# controller_rev4_1.net
KiCad netlist of a schematic drawn in EAGLE
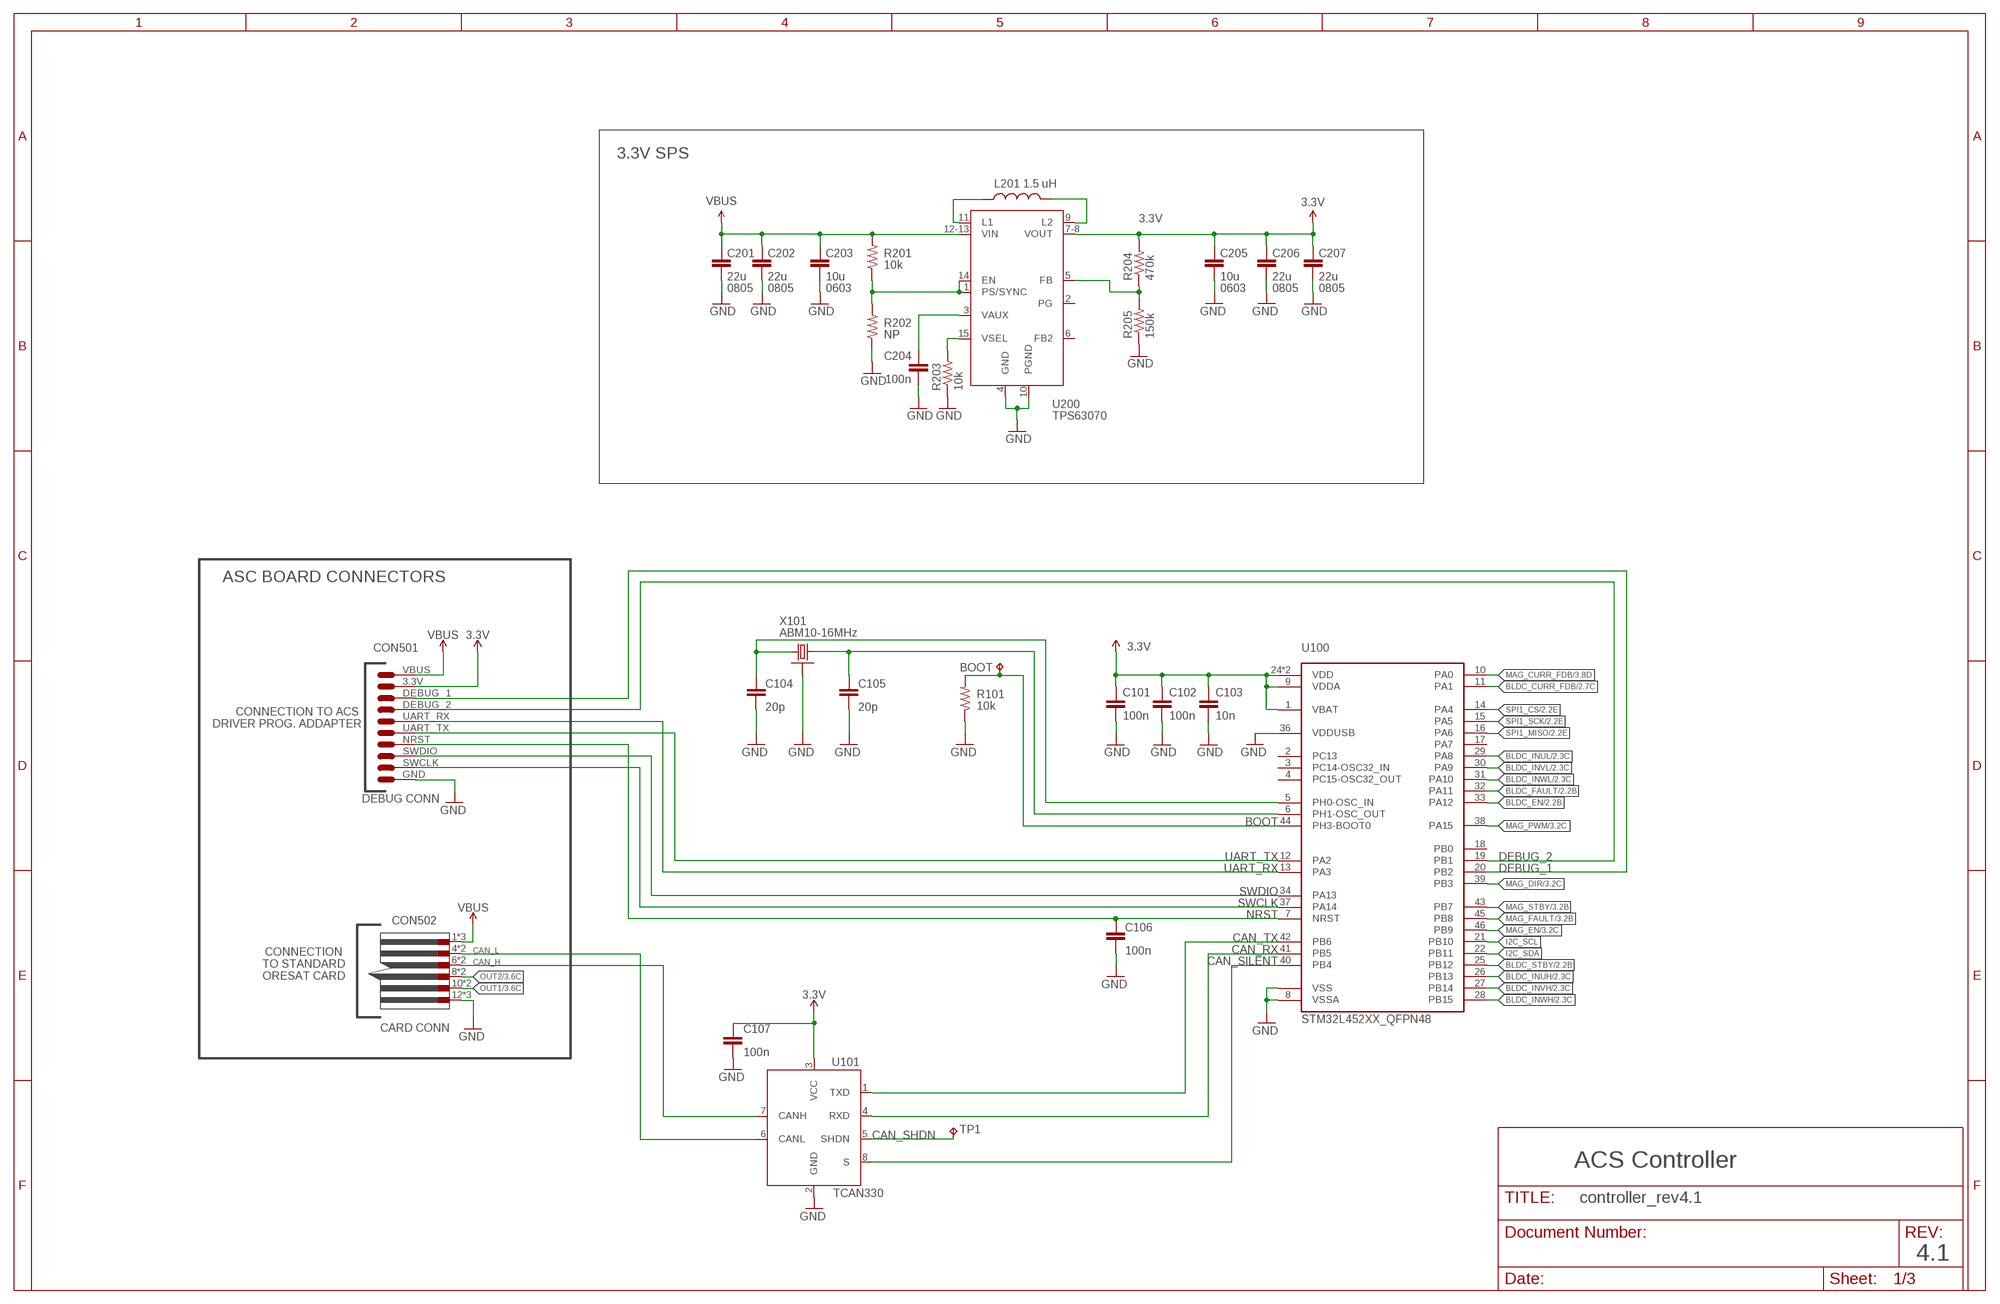
[diagram p0: schematic, sheet 1]
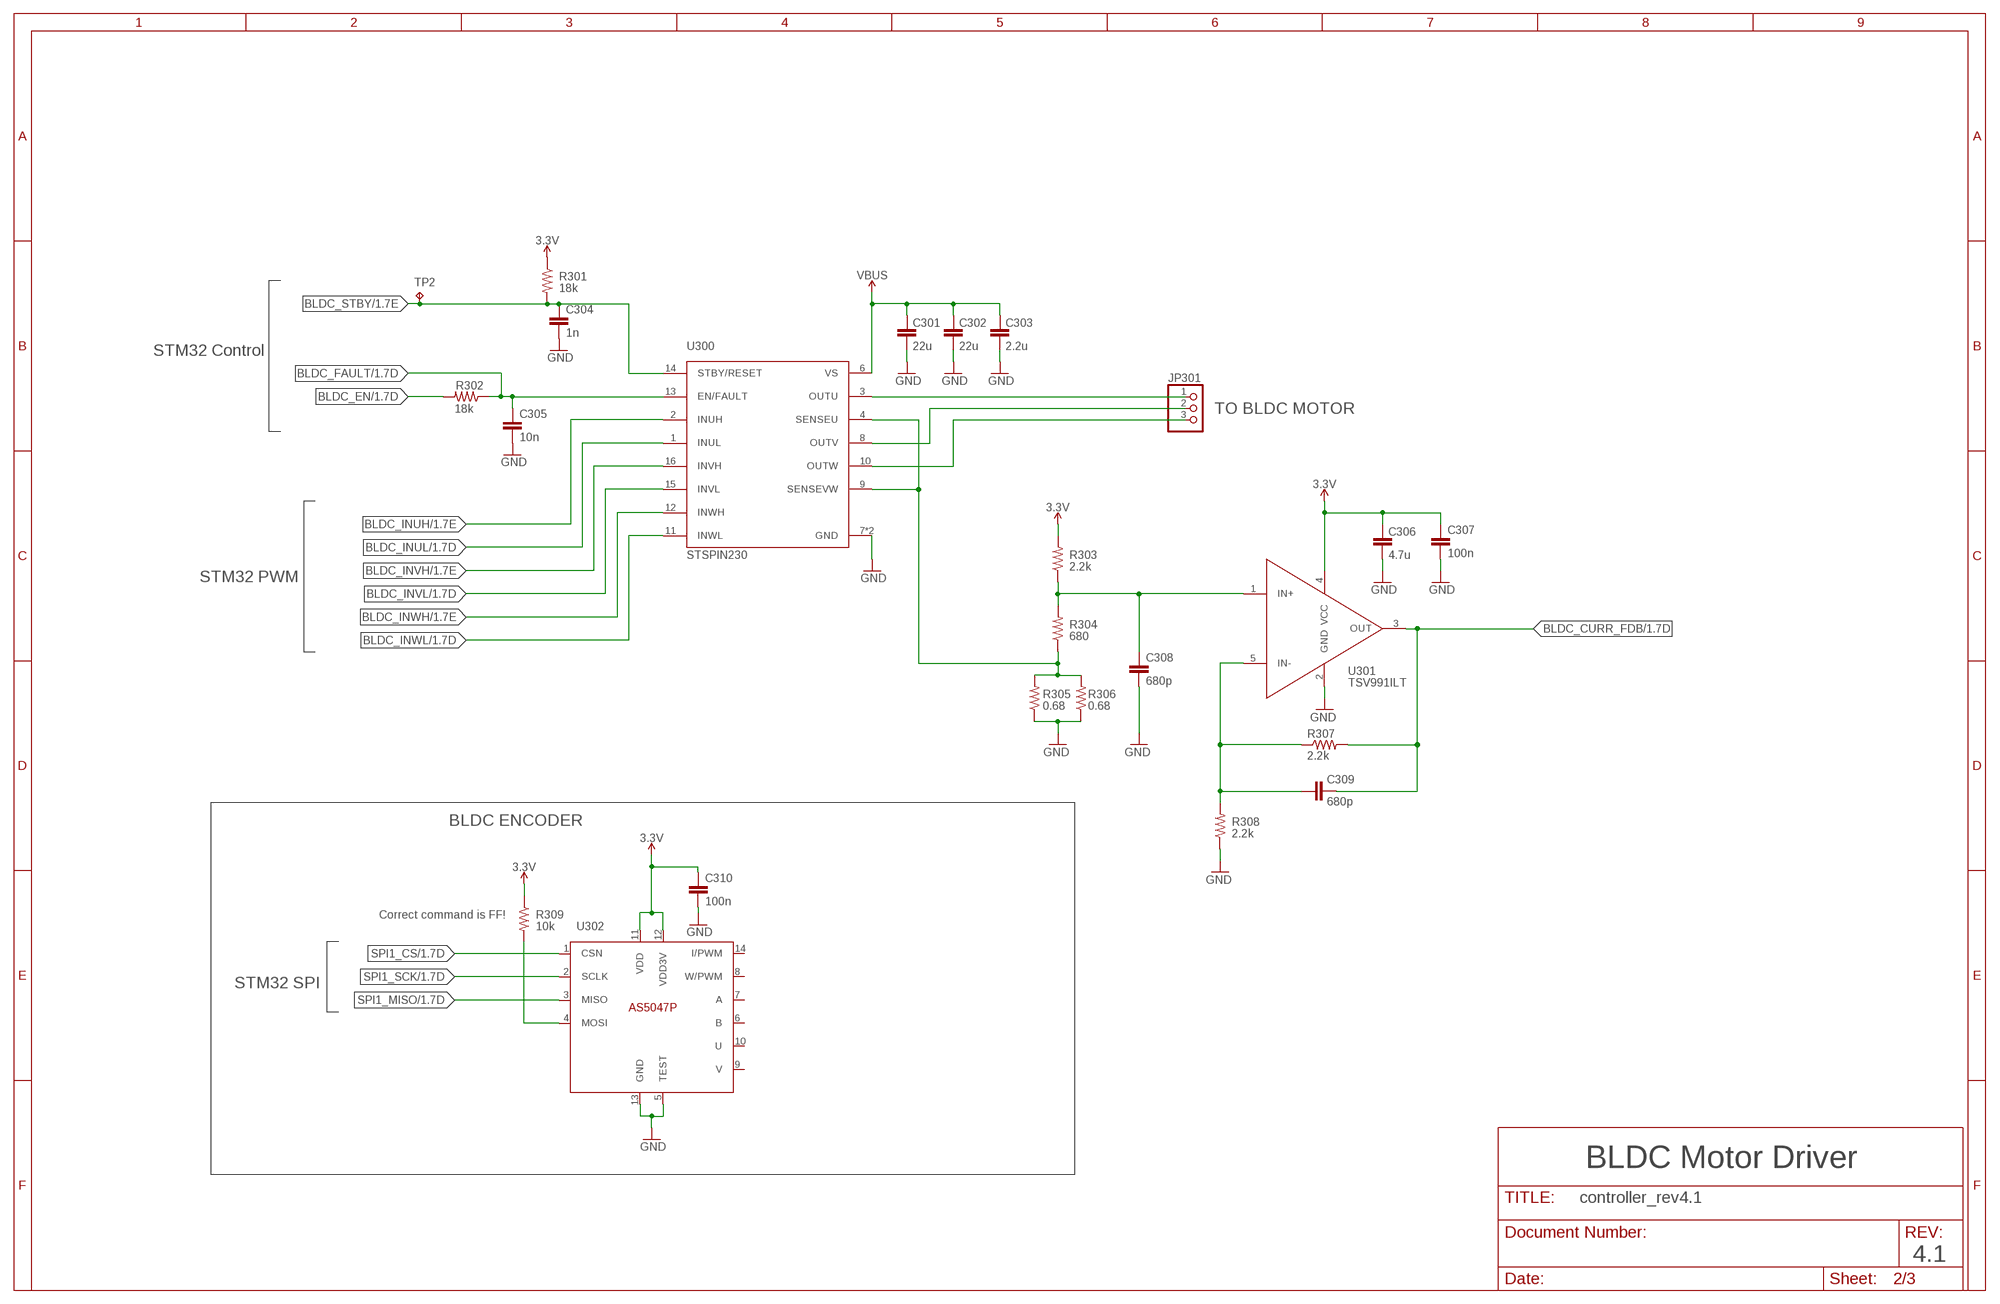
[diagram p1: schematic, sheet 2]
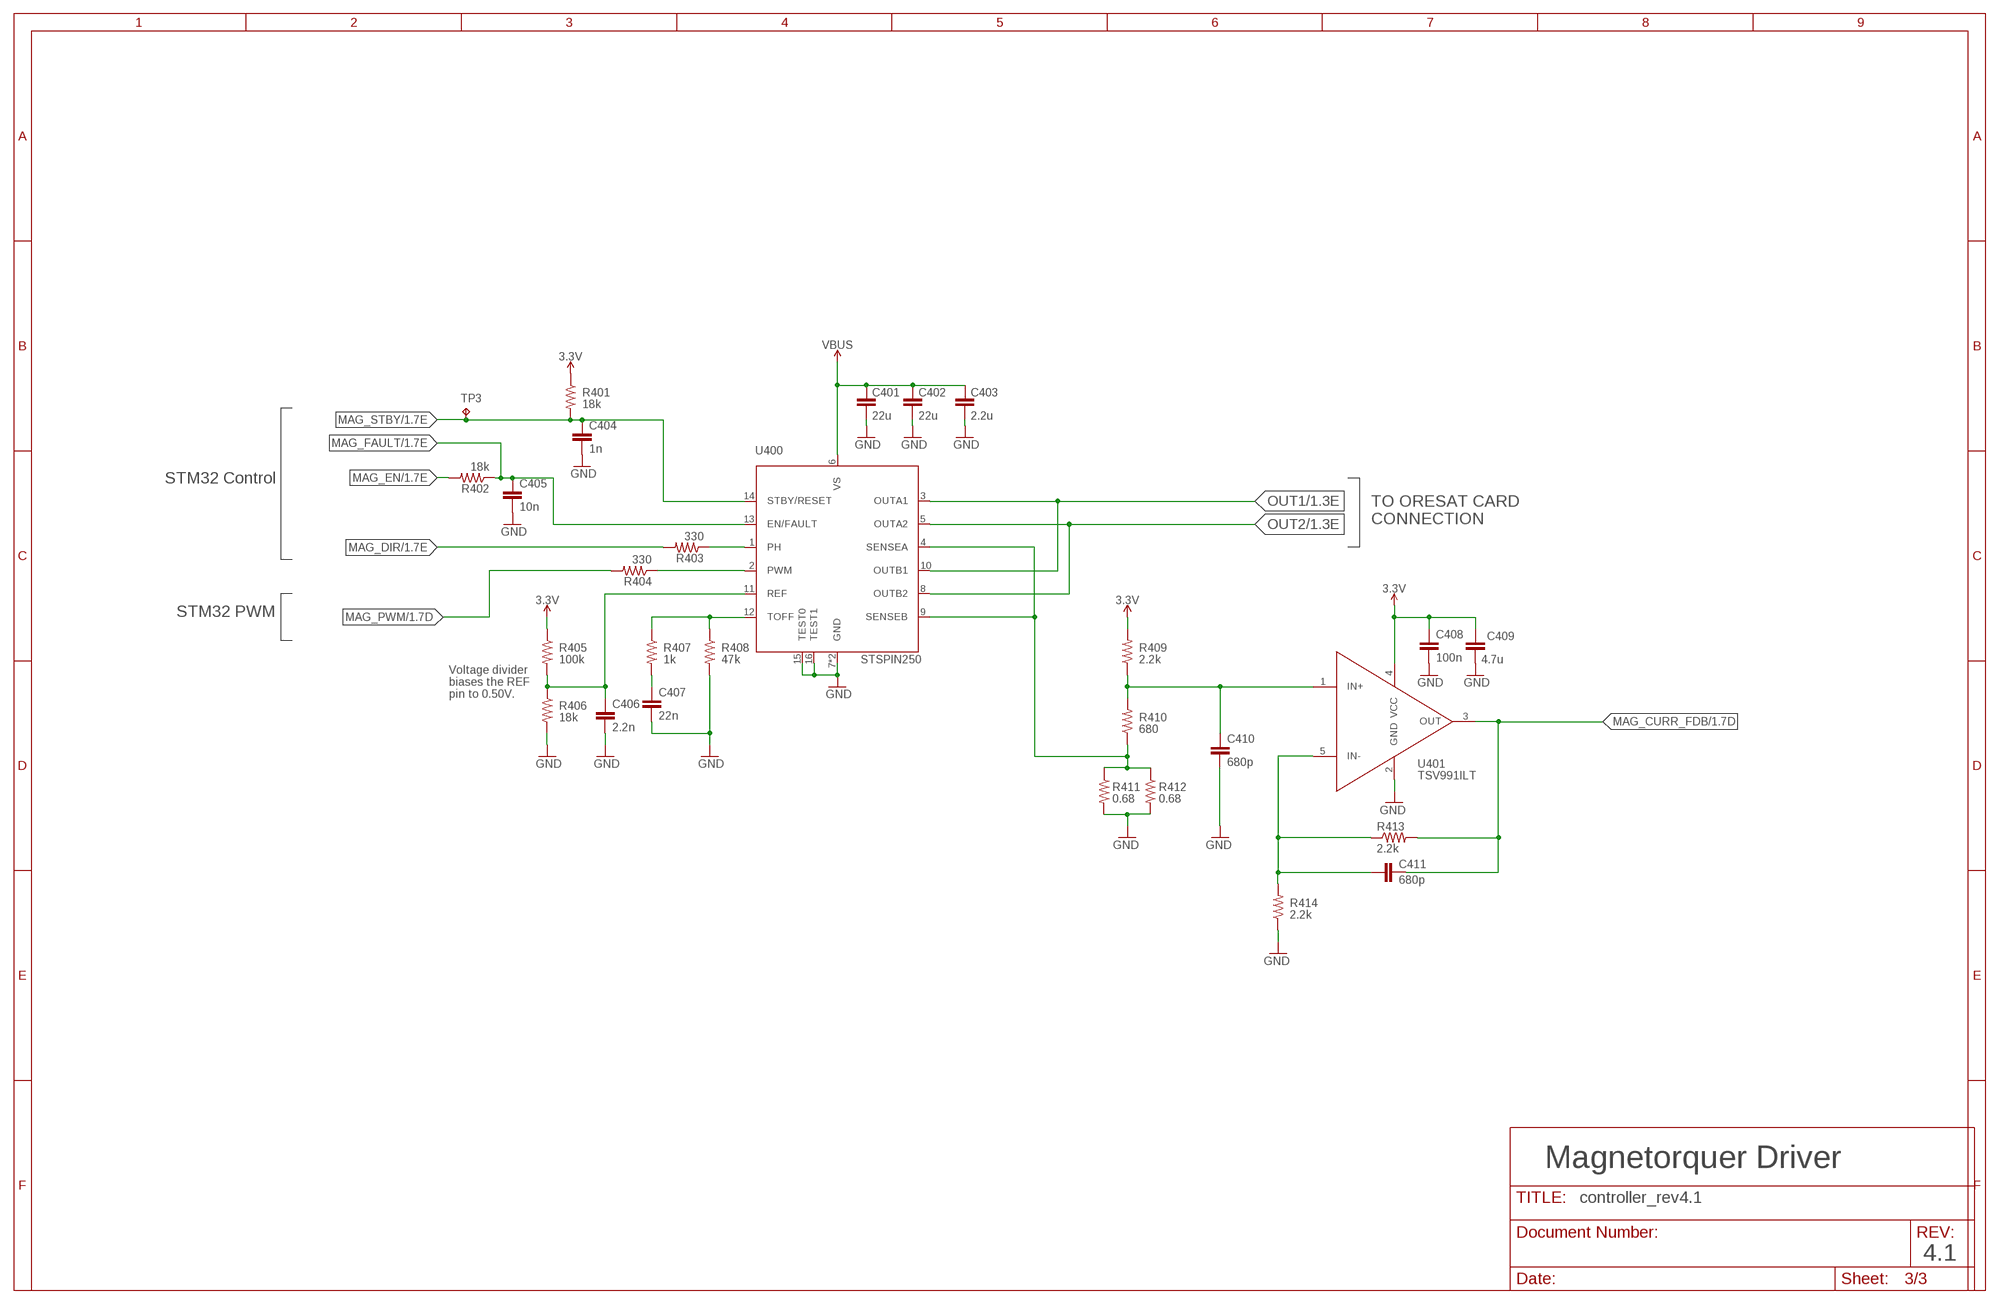
[diagram p2: schematic, sheet 3]

(export (version "E")
  (design (tool "Eeschema 10.0.6"))
  (components
    (comp (ref "C301")
      (value "22u")
      (footprint "eagle-import:.0603-B-NOSILK")
      (fields (field (name "MFR") "Samsung") (field (name "MPN") "CL05B104KO5NNNC"))
      (libsource (lib "eagle-import") (part "C-EU0603-B-NOSILK"))
    )
    (comp (ref "C302")
      (value "22u")
      (footprint "eagle-import:.0603-B-NOSILK")
      (fields (field (name "MFR") "Samsung") (field (name "MPN") "CL05B104KO5NNNC"))
      (libsource (lib "eagle-import") (part "C-EU0603-B-NOSILK"))
    )
    (comp (ref "C303")
      (value "2.2u")
      (footprint "eagle-import:.0603-B-NOSILK")
      (fields (field (name "MFR") "Samsung") (field (name "MPN") "CL05B104KO5NNNC"))
      (libsource (lib "eagle-import") (part "C-EU0603-B-NOSILK"))
    )
    (comp (ref "C304")
      (value "1n")
      (footprint "eagle-import:.0402-B-NOSILK")
      (fields (field (name "MFR") "Samsung") (field (name "MPN") "CL05B104KO5NNNC"))
      (libsource (lib "eagle-import") (part "rcl_custom_C-EU0402-B-NOSILK"))
    )
    (comp (ref "C305")
      (value "10n")
      (footprint "eagle-import:.0402-B-NOSILK")
      (fields (field (name "MFR") "Samsung") (field (name "MPN") "CL05B104KO5NNNC"))
      (libsource (lib "eagle-import") (part "rcl_custom_C-EU0402-B-NOSILK"))
    )
    (comp (ref "C306")
      (value "4.7u")
      (footprint "eagle-import:.0603-B-NOSILK")
      (fields (field (name "MFR") "Samsung") (field (name "MPN") "CL05B104KO5NNNC"))
      (libsource (lib "eagle-import") (part "C-EU0603-B-NOSILK"))
    )
    (comp (ref "C307")
      (value "100n")
      (footprint "eagle-import:.0402-B-NOSILK")
      (fields (field (name "MFR") "Samsung") (field (name "MPN") "CL05B104KO5NNNC"))
      (libsource (lib "eagle-import") (part "rcl_custom_C-EU0402-B-NOSILK"))
    )
    (comp (ref "C308")
      (value "680p")
      (footprint "eagle-import:.0402-B-NOSILK")
      (fields (field (name "MFR") "Samsung") (field (name "MPN") "CL05B104KO5NNNC"))
      (libsource (lib "eagle-import") (part "rcl_custom_C-EU0402-B-NOSILK"))
    )
    (comp (ref "C309")
      (value "680p")
      (footprint "eagle-import:.0402-B-NOSILK")
      (fields (field (name "MFR") "Samsung") (field (name "MPN") "CL05B104KO5NNNC"))
      (libsource (lib "eagle-import") (part "rcl_custom_C-EU0402-B-NOSILK"))
    )
    (comp (ref "C310")
      (value "100n")
      (footprint "eagle-import:.0402-B-NOSILK")
      (fields (field (name "MFR") "Samsung") (field (name "MPN") "CL05B104KO5NNNC"))
      (libsource (lib "eagle-import") (part "rcl_custom_C-EU0402-B-NOSILK"))
    )
    (comp (ref "JP301")
      (value "PINHD-1X03_2.00")
      (footprint "eagle-import:1X03M")
      (libsource (lib "eagle-import") (part "PINHD-1X03_2.00"))
    )
    (comp (ref "R301")
      (value "18k")
      (footprint "eagle-import:.0402-B-NOSILK")
      (fields (field (name "MFR") "Samsung") (field (name "MPN") "RC1005F6653CS"))
      (libsource (lib "eagle-import") (part "rcl_custom_R-US_0402-B-NOSILK"))
    )
    (comp (ref "R302")
      (value "18k")
      (footprint "eagle-import:.0402-B-NOSILK")
      (fields (field (name "MFR") "Samsung") (field (name "MPN") "RC1005F6653CS"))
      (libsource (lib "eagle-import") (part "rcl_custom_R-US_0402-B-NOSILK"))
    )
    (comp (ref "R303")
      (value "2.2k")
      (footprint "eagle-import:.0402-B-NOSILK")
      (fields (field (name "MFR") "Samsung") (field (name "MPN") "RC1005F6653CS"))
      (libsource (lib "eagle-import") (part "rcl_custom_R-US_0402-B-NOSILK"))
    )
    (comp (ref "R304")
      (value "680")
      (footprint "eagle-import:.0402-B-NOSILK")
      (fields (field (name "MFR") "Samsung") (field (name "MPN") "RC1005F6653CS"))
      (libsource (lib "eagle-import") (part "rcl_custom_R-US_0402-B-NOSILK"))
    )
    (comp (ref "R305")
      (value "0.68")
      (footprint "eagle-import:.0805-B-NOSILK")
      (libsource (lib "eagle-import") (part "R-US_0805-B-NOSILK"))
    )
    (comp (ref "R306")
      (value "0.68")
      (footprint "eagle-import:.0805-B-NOSILK")
      (libsource (lib "eagle-import") (part "R-US_0805-B-NOSILK"))
    )
    (comp (ref "R307")
      (value "2.2k")
      (footprint "eagle-import:.0402-B-NOSILK")
      (fields (field (name "MFR") "Samsung") (field (name "MPN") "RC1005F6653CS"))
      (libsource (lib "eagle-import") (part "rcl_custom_R-US_0402-B-NOSILK"))
    )
    (comp (ref "R308")
      (value "2.2k")
      (footprint "eagle-import:.0402-B-NOSILK")
      (fields (field (name "MFR") "Samsung") (field (name "MPN") "RC1005F6653CS"))
      (libsource (lib "eagle-import") (part "rcl_custom_R-US_0402-B-NOSILK"))
    )
    (comp (ref "R309")
      (value "10k")
      (footprint "eagle-import:.0402-B-NOSILK")
      (fields (field (name "MFR") "Samsung") (field (name "MPN") "RC1005F6653CS"))
      (libsource (lib "eagle-import") (part "rcl_custom_R-US_0402-B-NOSILK"))
    )
    (comp (ref "TP2")
      (value "TPTP06R")
      (footprint "eagle-import:TP06R")
      (libsource (lib "eagle-import") (part "TPTP06R"))
    )
    (comp (ref "U300")
      (value "STSPIN230")
      (footprint "eagle-import:VFQPN")
      (libsource (lib "eagle-import") (part "STSPIN230"))
    )
    (comp (ref "U301")
      (value "TSV991ILT")
      (footprint "eagle-import:SOT23-5")
      (libsource (lib "eagle-import") (part "TSV991ILT"))
    )
    (comp (ref "U302")
      (value "AS5047P")
      (footprint "eagle-import:TSSOP14")
      (libsource (lib "eagle-import") (part "AS5047P"))
    )
    (comp (ref "BOOT")
      (value "TPTP15SQ")
      (footprint "eagle-import:TP15SQ")
      (libsource (lib "eagle-import") (part "TPTP15SQ"))
    )
    (comp (ref "C101")
      (value "100n")
      (footprint "eagle-import:.0402-B-NOSILK")
      (fields (field (name "MFR") "Samsung") (field (name "MPN") "CL05B104KO5NNNC"))
      (libsource (lib "eagle-import") (part "rcl_custom_C-EU0402-B-NOSILK"))
    )
    (comp (ref "C102")
      (value "100n")
      (footprint "eagle-import:.0402-B-NOSILK")
      (fields (field (name "MFR") "Samsung") (field (name "MPN") "CL05B104KO5NNNC"))
      (libsource (lib "eagle-import") (part "rcl_custom_C-EU0402-B-NOSILK"))
    )
    (comp (ref "C103")
      (value "10n")
      (footprint "eagle-import:.0402-B-NOSILK")
      (fields (field (name "MFR") "Samsung") (field (name "MPN") "CL05B104KO5NNNC"))
      (libsource (lib "eagle-import") (part "rcl_custom_C-EU0402-B-NOSILK"))
    )
    (comp (ref "C104")
      (value "20p")
      (footprint "eagle-import:.0402-B-NOSILK")
      (fields (field (name "MFR") "Samsung") (field (name "MPN") "CL05C200JB51PNC"))
      (libsource (lib "eagle-import") (part "rcl_custom_C-EU0402-B-NOSILK"))
    )
    (comp (ref "C105")
      (value "20p")
      (footprint "eagle-import:.0402-B-NOSILK")
      (fields (field (name "MFR") "Samsung") (field (name "MPN") "CL05C200JB51PNC"))
      (libsource (lib "eagle-import") (part "rcl_custom_C-EU0402-B-NOSILK"))
    )
    (comp (ref "C106")
      (value "100n")
      (footprint "eagle-import:.0402-B-NOSILK")
      (fields (field (name "MFR") "Samsung") (field (name "MPN") "CL05C200JB51PNC"))
      (libsource (lib "eagle-import") (part "rcl_custom_C-EU0402-B-NOSILK"))
    )
    (comp (ref "C107")
      (value "100n")
      (footprint "eagle-import:.0402-B-NOSILK")
      (fields (field (name "MFR") "Samsung") (field (name "MPN") "CL05B104KO5NNNC"))
      (libsource (lib "eagle-import") (part "rcl_custom_C-EU0402-B-NOSILK"))
    )
    (comp (ref "C201")
      (value "22u")
      (footprint "eagle-import:.0805-B-NOSILK")
      (libsource (lib "eagle-import") (part "C-EU0805-B-NOSILK"))
    )
    (comp (ref "C202")
      (value "22u")
      (footprint "eagle-import:.0805-B-NOSILK")
      (libsource (lib "eagle-import") (part "C-EU0805-B-NOSILK"))
    )
    (comp (ref "C203")
      (value "10u")
      (footprint "eagle-import:.0603-B-NOSILK")
      (fields (field (name "MFR") "Samsung") (field (name "MPN") "CL05B104KO5NNNC"))
      (libsource (lib "eagle-import") (part "C-EU0603-B-NOSILK"))
    )
    (comp (ref "C204")
      (value "100n")
      (footprint "eagle-import:.0402-B-NOSILK")
      (fields (field (name "MFR") "Samsung") (field (name "MPN") "CL05B104KO5NNNC"))
      (libsource (lib "eagle-import") (part "rcl_custom_C-EU0402-B-NOSILK"))
    )
    (comp (ref "C205")
      (value "10u")
      (footprint "eagle-import:.0603-B-NOSILK")
      (fields (field (name "MFR") "Samsung") (field (name "MPN") "CL05B104KO5NNNC"))
      (libsource (lib "eagle-import") (part "C-EU0603-B-NOSILK"))
    )
    (comp (ref "C206")
      (value "22u")
      (footprint "eagle-import:.0805-B-NOSILK")
      (libsource (lib "eagle-import") (part "C-EU0805-B-NOSILK"))
    )
    (comp (ref "C207")
      (value "22u")
      (footprint "eagle-import:.0805-B-NOSILK")
      (libsource (lib "eagle-import") (part "C-EU0805-B-NOSILK"))
    )
    (comp (ref "C501")
      (value "DEBUG_CON")
      (footprint "eagle-import:DEBUG_CON")
      (libsource (lib "eagle-import") (part "DEBUG_CON"))
    )
    (comp (ref "CON502")
      (value "CARD CONN")
      (footprint "eagle-import:LOW-PROFILE_CONNECTOR(TAB)")
      (libsource (lib "eagle-import") (part "LOW-PROFILE_CONNECTOR(TAB)"))
    )
    (comp (ref "L201")
      (value "1.5 uH")
      (footprint "eagle-import:L-COILCRAFT-XFL4020")
      (fields (field (name "MFR") "Coilcraft") (field (name "MPN") "XFL4020-152ME"))
      (libsource (lib "eagle-import") (part "L-COILCRAFT-XFL4020"))
    )
    (comp (ref "R101")
      (value "10k")
      (footprint "eagle-import:.0402-B-NOSILK")
      (fields (field (name "MFR") "Samsung") (field (name "MPN") "RC1005F6653CS"))
      (libsource (lib "eagle-import") (part "rcl_custom_R-US_0402-B-NOSILK"))
    )
    (comp (ref "R201")
      (value "10k")
      (footprint "eagle-import:.0402-B-NOSILK")
      (fields (field (name "MFR") "Samsung") (field (name "MPN") "RC1005F6653CS"))
      (libsource (lib "eagle-import") (part "rcl_custom_R-US_0402-B-NOSILK"))
    )
    (comp (ref "R202")
      (value "NP")
      (footprint "eagle-import:.0402-B-NOSILK")
      (fields (field (name "MFR") "Samsung") (field (name "MPN") "RC1005F6653CS"))
      (libsource (lib "eagle-import") (part "rcl_custom_R-US_0402-B-NOSILK"))
    )
    (comp (ref "R203")
      (value "10k")
      (footprint "eagle-import:.0402-B-NOSILK")
      (fields (field (name "MFR") "Samsung") (field (name "MPN") "RC1005F6653CS"))
      (libsource (lib "eagle-import") (part "rcl_custom_R-US_0402-B-NOSILK"))
    )
    (comp (ref "R204")
      (value "470k")
      (footprint "eagle-import:.0402-B-NOSILK")
      (fields (field (name "MFR") "Samsung") (field (name "MPN") "RC1005F6653CS"))
      (libsource (lib "eagle-import") (part "rcl_custom_R-US_0402-B-NOSILK"))
    )
    (comp (ref "R205")
      (value "150k")
      (footprint "eagle-import:.0402-B-NOSILK")
      (fields (field (name "MFR") "Samsung") (field (name "MPN") "RC1005F6653CS"))
      (libsource (lib "eagle-import") (part "rcl_custom_R-US_0402-B-NOSILK"))
    )
    (comp (ref "TP1")
      (value "TPTP06R")
      (footprint "eagle-import:TP06R")
      (libsource (lib "eagle-import") (part "TPTP06R"))
    )
    (comp (ref "U100")
      (value "STM32L452XX_QFPN48")
      (footprint "eagle-import:QFPN-48")
      (libsource (lib "eagle-import") (part "STM32L452XX_QFPN48"))
    )
    (comp (ref "U101")
      (value "TCAN330")
      (footprint "eagle-import:SOT23-8_TI-DCN")
      (fields (field (name "MFR") "Texas Instruments") (field (name "MPN") "TCAN330GDCNT"))
      (libsource (lib "eagle-import") (part "TCAN330"))
    )
    (comp (ref "U200")
      (value "TPS63070")
      (footprint "eagle-import:TPS63070X")
      (fields (field (name "MFR") "TI"))
      (libsource (lib "eagle-import") (part "TPS63070X"))
    )
    (comp (ref "X101")
      (value "ABM10-16MHz")
      (footprint "eagle-import:CRYSTAL_2.5X2")
      (fields (field (name "MFR") "ECS Inc.") (field (name "MPN") "ECS-160-10-36Q-ES-TR"))
      (libsource (lib "eagle-import") (part "CRYSTAL-WITH-GND"))
    )
    (comp (ref "C401")
      (value "22u")
      (footprint "eagle-import:.0603-B-NOSILK")
      (fields (field (name "MFR") "Samsung") (field (name "MPN") "CL05B104KO5NNNC"))
      (libsource (lib "eagle-import") (part "C-EU0603-B-NOSILK"))
    )
    (comp (ref "C402")
      (value "22u")
      (footprint "eagle-import:.0603-B-NOSILK")
      (fields (field (name "MFR") "Samsung") (field (name "MPN") "CL05B104KO5NNNC"))
      (libsource (lib "eagle-import") (part "C-EU0603-B-NOSILK"))
    )
    (comp (ref "C403")
      (value "2.2u")
      (footprint "eagle-import:.0603-B-NOSILK")
      (fields (field (name "MFR") "Samsung") (field (name "MPN") "CL05B104KO5NNNC"))
      (libsource (lib "eagle-import") (part "C-EU0603-B-NOSILK"))
    )
    (comp (ref "C404")
      (value "1n")
      (footprint "eagle-import:.0402-B-NOSILK")
      (fields (field (name "MFR") "Samsung") (field (name "MPN") "CL05B104KO5NNNC"))
      (libsource (lib "eagle-import") (part "rcl_custom_C-EU0402-B-NOSILK"))
    )
    (comp (ref "C405")
      (value "10n")
      (footprint "eagle-import:.0402-B-NOSILK")
      (fields (field (name "MFR") "Samsung") (field (name "MPN") "CL05B104KO5NNNC"))
      (libsource (lib "eagle-import") (part "rcl_custom_C-EU0402-B-NOSILK"))
    )
    (comp (ref "C406")
      (value "2.2n")
      (footprint "eagle-import:.0402-B-NOSILK")
      (fields (field (name "MFR") "Samsung") (field (name "MPN") "CL05B104KO5NNNC"))
      (libsource (lib "eagle-import") (part "rcl_custom_C-EU0402-B-NOSILK"))
    )
    (comp (ref "C407")
      (value "22n")
      (footprint "eagle-import:.0402-B-NOSILK")
      (fields (field (name "MFR") "Samsung") (field (name "MPN") "CL05B104KO5NNNC"))
      (libsource (lib "eagle-import") (part "rcl_custom_C-EU0402-B-NOSILK"))
    )
    (comp (ref "C408")
      (value "100n")
      (footprint "eagle-import:.0402-B-NOSILK")
      (fields (field (name "MFR") "Samsung") (field (name "MPN") "CL05B104KO5NNNC"))
      (libsource (lib "eagle-import") (part "rcl_custom_C-EU0402-B-NOSILK"))
    )
    (comp (ref "C409")
      (value "4.7u")
      (footprint "eagle-import:.0603-B-NOSILK")
      (fields (field (name "MFR") "Samsung") (field (name "MPN") "CL05B104KO5NNNC"))
      (libsource (lib "eagle-import") (part "C-EU0603-B-NOSILK"))
    )
    (comp (ref "C410")
      (value "680p")
      (footprint "eagle-import:.0402-B-NOSILK")
      (fields (field (name "MFR") "Samsung") (field (name "MPN") "CL05B104KO5NNNC"))
      (libsource (lib "eagle-import") (part "rcl_custom_C-EU0402-B-NOSILK"))
    )
    (comp (ref "C411")
      (value "680p")
      (footprint "eagle-import:.0402-B-NOSILK")
      (fields (field (name "MFR") "Samsung") (field (name "MPN") "CL05B104KO5NNNC"))
      (libsource (lib "eagle-import") (part "rcl_custom_C-EU0402-B-NOSILK"))
    )
    (comp (ref "R401")
      (value "18k")
      (footprint "eagle-import:.0402-B-NOSILK")
      (fields (field (name "MFR") "Samsung") (field (name "MPN") "RC1005F6653CS"))
      (libsource (lib "eagle-import") (part "rcl_custom_R-US_0402-B-NOSILK"))
    )
    (comp (ref "R402")
      (value "18k")
      (footprint "eagle-import:.0402-B-NOSILK")
      (fields (field (name "MFR") "Samsung") (field (name "MPN") "RC1005F6653CS"))
      (libsource (lib "eagle-import") (part "rcl_custom_R-US_0402-B-NOSILK"))
    )
    (comp (ref "R403")
      (value "330")
      (footprint "eagle-import:.0402-B-NOSILK")
      (fields (field (name "MFR") "Samsung") (field (name "MPN") "RC1005F6653CS"))
      (libsource (lib "eagle-import") (part "rcl_custom_R-US_0402-B-NOSILK"))
    )
    (comp (ref "R404")
      (value "330")
      (footprint "eagle-import:.0402-B-NOSILK")
      (fields (field (name "MFR") "Samsung") (field (name "MPN") "RC1005F6653CS"))
      (libsource (lib "eagle-import") (part "rcl_custom_R-US_0402-B-NOSILK"))
    )
    (comp (ref "R405")
      (value "100k")
      (footprint "eagle-import:.0402-B-NOSILK")
      (fields (field (name "MFR") "Samsung") (field (name "MPN") "RC1005F6653CS"))
      (libsource (lib "eagle-import") (part "rcl_custom_R-US_0402-B-NOSILK"))
    )
    (comp (ref "R406")
      (value "18k")
      (footprint "eagle-import:.0402-B-NOSILK")
      (fields (field (name "MFR") "Samsung") (field (name "MPN") "RC1005F6653CS"))
      (libsource (lib "eagle-import") (part "rcl_custom_R-US_0402-B-NOSILK"))
    )
    (comp (ref "R407")
      (value "1k")
      (footprint "eagle-import:.0402-B-NOSILK")
      (fields (field (name "MFR") "Samsung") (field (name "MPN") "RC1005F6653CS"))
      (libsource (lib "eagle-import") (part "rcl_custom_R-US_0402-B-NOSILK"))
    )
    (comp (ref "R408")
      (value "47k")
      (footprint "eagle-import:.0402-B-NOSILK")
      (fields (field (name "MFR") "Samsung") (field (name "MPN") "RC1005F6653CS"))
      (libsource (lib "eagle-import") (part "rcl_custom_R-US_0402-B-NOSILK"))
    )
    (comp (ref "R409")
      (value "2.2k")
      (footprint "eagle-import:.0402-B-NOSILK")
      (fields (field (name "MFR") "Samsung") (field (name "MPN") "RC1005F6653CS"))
      (libsource (lib "eagle-import") (part "rcl_custom_R-US_0402-B-NOSILK"))
    )
    (comp (ref "R410")
      (value "680")
      (footprint "eagle-import:.0402-B-NOSILK")
      (fields (field (name "MFR") "Samsung") (field (name "MPN") "RC1005F6653CS"))
      (libsource (lib "eagle-import") (part "rcl_custom_R-US_0402-B-NOSILK"))
    )
    (comp (ref "R411")
      (value "0.68")
      (footprint "eagle-import:.0805-B-NOSILK")
      (libsource (lib "eagle-import") (part "R-US_0805-B-NOSILK"))
    )
    (comp (ref "R412")
      (value "0.68")
      (footprint "eagle-import:.0805-B-NOSILK")
      (libsource (lib "eagle-import") (part "R-US_0805-B-NOSILK"))
    )
    (comp (ref "R413")
      (value "2.2k")
      (footprint "eagle-import:.0402-B-NOSILK")
      (fields (field (name "MFR") "Samsung") (field (name "MPN") "RC1005F6653CS"))
      (libsource (lib "eagle-import") (part "rcl_custom_R-US_0402-B-NOSILK"))
    )
    (comp (ref "R414")
      (value "2.2k")
      (footprint "eagle-import:.0402-B-NOSILK")
      (fields (field (name "MFR") "Samsung") (field (name "MPN") "RC1005F6653CS"))
      (libsource (lib "eagle-import") (part "rcl_custom_R-US_0402-B-NOSILK"))
    )
    (comp (ref "TP3")
      (value "TPTP06R")
      (footprint "eagle-import:TP06R")
      (libsource (lib "eagle-import") (part "TPTP06R"))
    )
    (comp (ref "U400")
      (value "STSPIN250")
      (footprint "eagle-import:VFQPN")
      (libsource (lib "eagle-import") (part "STSPIN250"))
    )
    (comp (ref "U401")
      (value "TSV991ILT")
      (footprint "eagle-import:SOT23-5")
      (libsource (lib "eagle-import") (part "TSV991ILT"))
    )
  )
  (nets
    (net (code "1") (name "3.3V") (class "Default")
      (node (ref "C101") (pin "1") (pinfunction "1_1") (pintype "passive"))
      (node (ref "C102") (pin "1") (pinfunction "1_1") (pintype "passive"))
      (node (ref "C103") (pin "1") (pinfunction "1_1") (pintype "passive"))
      (node (ref "C107") (pin "1") (pinfunction "1_1") (pintype "passive"))
      (node (ref "C205") (pin "1") (pinfunction "1_1") (pintype "passive"))
      (node (ref "C206") (pin "1") (pinfunction "1_1") (pintype "passive"))
      (node (ref "C207") (pin "1") (pinfunction "1_1") (pintype "passive"))
      (node (ref "C306") (pin "1") (pinfunction "1_1") (pintype "passive"))
      (node (ref "C307") (pin "1") (pinfunction "1_1") (pintype "passive"))
      (node (ref "C310") (pin "1") (pinfunction "1_1") (pintype "passive"))
      (node (ref "C408") (pin "1") (pinfunction "1_1") (pintype "passive"))
      (node (ref "C409") (pin "1") (pinfunction "1_1") (pintype "passive"))
      (node (ref "C501") (pin "3.3V") (pinfunction "2_3.3V") (pintype "bidirectional"))
      (node (ref "R204") (pin "2") (pinfunction "2_2") (pintype "passive"))
      (node (ref "R301") (pin "1") (pinfunction "1_1") (pintype "passive"))
      (node (ref "R303") (pin "2") (pinfunction "2_2") (pintype "passive"))
      (node (ref "R309") (pin "1") (pinfunction "1_1") (pintype "passive"))
      (node (ref "R401") (pin "1") (pinfunction "1_1") (pintype "passive"))
      (node (ref "R405") (pin "1") (pinfunction "1_1") (pintype "passive"))
      (node (ref "R409") (pin "2") (pinfunction "2_2") (pintype "passive"))
      (node (ref "U100") (pin "1") (pinfunction "VBAT_1") (pintype "bidirectional"))
      (node (ref "U100") (pin "24") (pinfunction "VDD_24") (pintype "bidirectional"))
      (node (ref "U100") (pin "48") (pinfunction "VDD_48") (pintype "bidirectional"))
      (node (ref "U100") (pin "9") (pinfunction "VDDA_9") (pintype "bidirectional"))
      (node (ref "U101") (pin "3") (pinfunction "VCC_3") (pintype "power_in"))
      (node (ref "U200") (pin "7-8") (pinfunction "VOUT_7-8") (pintype "power_in"))
      (node (ref "U301") (pin "4") (pinfunction "VCC_4") (pintype "bidirectional"))
      (node (ref "U302") (pin "11") (pinfunction "VDD_11") (pintype "power_in"))
      (node (ref "U302") (pin "12") (pinfunction "VDD3V_12") (pintype "power_in"))
      (node (ref "U401") (pin "4") (pinfunction "VCC_4") (pintype "bidirectional"))
    )
    (net (code "2") (name "BLDC_CURR_FDB") (class "Default")
      (node (ref "C309") (pin "1") (pinfunction "1_1") (pintype "passive"))
      (node (ref "R307") (pin "2") (pinfunction "2_2") (pintype "passive"))
      (node (ref "U100") (pin "11") (pinfunction "PA1_11") (pintype "bidirectional"))
      (node (ref "U301") (pin "3") (pinfunction "OUT_3") (pintype "bidirectional"))
    )
    (net (code "3") (name "BLDC_EN") (class "Default")
      (node (ref "R302") (pin "2") (pinfunction "2_2") (pintype "passive"))
      (node (ref "U100") (pin "33") (pinfunction "PA12_33") (pintype "bidirectional"))
    )
    (net (code "4") (name "BLDC_FAULT") (class "Default")
      (node (ref "C305") (pin "1") (pinfunction "1_1") (pintype "passive"))
      (node (ref "R302") (pin "1") (pinfunction "1_1") (pintype "passive"))
      (node (ref "U100") (pin "32") (pinfunction "PA11_32") (pintype "bidirectional"))
      (node (ref "U300") (pin "13") (pinfunction "EN/FAULT_13") (pintype "bidirectional"))
    )
    (net (code "5") (name "BLDC_INUH") (class "Default")
      (node (ref "U100") (pin "26") (pinfunction "PB13_26") (pintype "bidirectional"))
      (node (ref "U300") (pin "2") (pinfunction "INUH_2") (pintype "input"))
    )
    (net (code "6") (name "BLDC_INUL") (class "Default")
      (node (ref "U100") (pin "29") (pinfunction "PA8_29") (pintype "bidirectional"))
      (node (ref "U300") (pin "1") (pinfunction "INUL_1") (pintype "input"))
    )
    (net (code "7") (name "BLDC_INVH") (class "Default")
      (node (ref "U100") (pin "27") (pinfunction "PB14_27") (pintype "bidirectional"))
      (node (ref "U300") (pin "16") (pinfunction "INVH_16") (pintype "input"))
    )
    (net (code "8") (name "BLDC_INVL") (class "Default")
      (node (ref "U100") (pin "30") (pinfunction "PA9_30") (pintype "bidirectional"))
      (node (ref "U300") (pin "15") (pinfunction "INVL_15") (pintype "input"))
    )
    (net (code "9") (name "BLDC_INWH") (class "Default")
      (node (ref "U100") (pin "28") (pinfunction "PB15_28") (pintype "bidirectional"))
      (node (ref "U300") (pin "12") (pinfunction "INWH_12") (pintype "input"))
    )
    (net (code "10") (name "BLDC_INWL") (class "Default")
      (node (ref "U100") (pin "31") (pinfunction "PA10_31") (pintype "bidirectional"))
      (node (ref "U300") (pin "11") (pinfunction "INWL_11") (pintype "input"))
    )
    (net (code "11") (name "BLDC_STBY") (class "Default")
      (node (ref "C304") (pin "1") (pinfunction "1_1") (pintype "passive"))
      (node (ref "R301") (pin "2") (pinfunction "2_2") (pintype "passive"))
      (node (ref "TP2") (pin "TP") (pinfunction "TP_TP") (pintype "input"))
      (node (ref "U100") (pin "25") (pinfunction "PB12_25") (pintype "bidirectional"))
      (node (ref "U300") (pin "14") (pinfunction "STBY/RESET_14") (pintype "input"))
    )
    (net (code "12") (name "BOOT") (class "Default")
      (node (ref "BOOT") (pin "TP") (pinfunction "TP_TP") (pintype "input"))
      (node (ref "R101") (pin "2") (pinfunction "2_2") (pintype "passive"))
      (node (ref "U100") (pin "44") (pinfunction "PH3-BOOT0_44") (pintype "bidirectional"))
    )
    (net (code "13") (name "CAN_H") (class "Default")
      (node (ref "CON502") (pin "6") (pinfunction "3_6") (pintype "bidirectional"))
      (node (ref "CON502") (pin "7") (pinfunction "3_7") (pintype "bidirectional"))
      (node (ref "U101") (pin "7") (pinfunction "CANH_7") (pintype "bidirectional"))
    )
    (net (code "14") (name "CAN_L") (class "Default")
      (node (ref "CON502") (pin "4") (pinfunction "2_4") (pintype "bidirectional"))
      (node (ref "CON502") (pin "5") (pinfunction "2_5") (pintype "bidirectional"))
      (node (ref "U101") (pin "6") (pinfunction "CANL_6") (pintype "bidirectional"))
    )
    (net (code "15") (name "CAN_RX") (class "Default")
      (node (ref "U100") (pin "41") (pinfunction "PB5_41") (pintype "bidirectional"))
      (node (ref "U101") (pin "4") (pinfunction "RXD_4") (pintype "output"))
    )
    (net (code "16") (name "CAN_SHDN") (class "Default")
      (node (ref "TP1") (pin "TP") (pinfunction "TP_TP") (pintype "input"))
      (node (ref "U101") (pin "5") (pinfunction "SHDN_5") (pintype "input"))
    )
    (net (code "17") (name "CAN_SILENT") (class "Default")
      (node (ref "U100") (pin "40") (pinfunction "PB4_40") (pintype "bidirectional"))
      (node (ref "U101") (pin "8") (pinfunction "S_8") (pintype "input"))
    )
    (net (code "18") (name "CAN_TX") (class "Default")
      (node (ref "U100") (pin "42") (pinfunction "PB6_42") (pintype "bidirectional"))
      (node (ref "U101") (pin "1") (pinfunction "TXD_1") (pintype "input"))
    )
    (net (code "19") (name "DEBUG_1") (class "Default")
      (node (ref "C501") (pin "DEBUG_1") (pinfunction "3_DEBUG_1") (pintype "bidirectional"))
      (node (ref "U100") (pin "20") (pinfunction "PB2_20") (pintype "bidirectional"))
    )
    (net (code "20") (name "DEBUG_2") (class "Default")
      (node (ref "C501") (pin "DEBUG_2") (pinfunction "4_DEBUG_2") (pintype "bidirectional"))
      (node (ref "U100") (pin "19") (pinfunction "PB1_19") (pintype "bidirectional"))
    )
    (net (code "21") (name "GND") (class "Default")
      (node (ref "C101") (pin "2") (pinfunction "2_2") (pintype "passive"))
      (node (ref "C102") (pin "2") (pinfunction "2_2") (pintype "passive"))
      (node (ref "C103") (pin "2") (pinfunction "2_2") (pintype "passive"))
      (node (ref "C104") (pin "2") (pinfunction "2_2") (pintype "passive"))
      (node (ref "C105") (pin "2") (pinfunction "2_2") (pintype "passive"))
      (node (ref "C106") (pin "2") (pinfunction "2_2") (pintype "passive"))
      (node (ref "C107") (pin "2") (pinfunction "2_2") (pintype "passive"))
      (node (ref "C201") (pin "2") (pinfunction "2_2") (pintype "passive"))
      (node (ref "C202") (pin "2") (pinfunction "2_2") (pintype "passive"))
      (node (ref "C203") (pin "2") (pinfunction "2_2") (pintype "passive"))
      (node (ref "C204") (pin "2") (pinfunction "2_2") (pintype "passive"))
      (node (ref "C205") (pin "2") (pinfunction "2_2") (pintype "passive"))
      (node (ref "C206") (pin "2") (pinfunction "2_2") (pintype "passive"))
      (node (ref "C207") (pin "2") (pinfunction "2_2") (pintype "passive"))
      (node (ref "C301") (pin "2") (pinfunction "2_2") (pintype "passive"))
      (node (ref "C302") (pin "2") (pinfunction "2_2") (pintype "passive"))
      (node (ref "C303") (pin "2") (pinfunction "2_2") (pintype "passive"))
      (node (ref "C304") (pin "2") (pinfunction "2_2") (pintype "passive"))
      (node (ref "C305") (pin "2") (pinfunction "2_2") (pintype "passive"))
      (node (ref "C306") (pin "2") (pinfunction "2_2") (pintype "passive"))
      (node (ref "C307") (pin "2") (pinfunction "2_2") (pintype "passive"))
      (node (ref "C308") (pin "2") (pinfunction "2_2") (pintype "passive"))
      (node (ref "C310") (pin "2") (pinfunction "2_2") (pintype "passive"))
      (node (ref "C401") (pin "2") (pinfunction "2_2") (pintype "passive"))
      (node (ref "C402") (pin "2") (pinfunction "2_2") (pintype "passive"))
      (node (ref "C403") (pin "2") (pinfunction "2_2") (pintype "passive"))
      (node (ref "C404") (pin "2") (pinfunction "2_2") (pintype "passive"))
      (node (ref "C405") (pin "2") (pinfunction "2_2") (pintype "passive"))
      (node (ref "C406") (pin "2") (pinfunction "2_2") (pintype "passive"))
      (node (ref "C407") (pin "2") (pinfunction "2_2") (pintype "passive"))
      (node (ref "C408") (pin "2") (pinfunction "2_2") (pintype "passive"))
      (node (ref "C409") (pin "2") (pinfunction "2_2") (pintype "passive"))
      (node (ref "C410") (pin "2") (pinfunction "2_2") (pintype "passive"))
      (node (ref "C501") (pin "GND") (pinfunction "10_GND") (pintype "bidirectional"))
      (node (ref "CON502") (pin "12") (pinfunction "6_12") (pintype "bidirectional"))
      (node (ref "CON502") (pin "13") (pinfunction "6_13") (pintype "bidirectional"))
      (node (ref "CON502") (pin "14") (pinfunction "6_14") (pintype "bidirectional"))
      (node (ref "R101") (pin "1") (pinfunction "1_1") (pintype "passive"))
      (node (ref "R202") (pin "1") (pinfunction "1_1") (pintype "passive"))
      (node (ref "R203") (pin "1") (pinfunction "1_1") (pintype "passive"))
      (node (ref "R205") (pin "1") (pinfunction "1_1") (pintype "passive"))
      (node (ref "R305") (pin "1") (pinfunction "1_1") (pintype "passive"))
      (node (ref "R306") (pin "1") (pinfunction "1_1") (pintype "passive"))
      (node (ref "R308") (pin "1") (pinfunction "1_1") (pintype "passive"))
      (node (ref "R406") (pin "2") (pinfunction "2_2") (pintype "passive"))
      (node (ref "R408") (pin "2") (pinfunction "2_2") (pintype "passive"))
      (node (ref "R411") (pin "2") (pinfunction "2_2") (pintype "passive"))
      (node (ref "R412") (pin "2") (pinfunction "2_2") (pintype "passive"))
      (node (ref "R414") (pin "1") (pinfunction "1_1") (pintype "passive"))
      (node (ref "U100") (pin "23") (pinfunction "VSS_23") (pintype "bidirectional"))
      (node (ref "U100") (pin "35") (pinfunction "VSS_35") (pintype "bidirectional"))
      (node (ref "U100") (pin "36") (pinfunction "VDDUSB_36") (pintype "bidirectional"))
      (node (ref "U100") (pin "47") (pinfunction "VSS_47") (pintype "bidirectional"))
      (node (ref "U100") (pin "8") (pinfunction "VSSA_8") (pintype "bidirectional"))
      (node (ref "U100") (pin "EPAD") (pinfunction "VSS_EPAD") (pintype "bidirectional"))
      (node (ref "U101") (pin "2") (pinfunction "GND_2") (pintype "power_in"))
      (node (ref "U200") (pin "10") (pinfunction "PGND_10") (pintype "power_in"))
      (node (ref "U200") (pin "4") (pinfunction "GND_4") (pintype "power_in"))
      (node (ref "U300") (pin "7") (pinfunction "GND_7") (pintype "power_in"))
      (node (ref "U300") (pin "EPAD") (pinfunction "GND_EPAD") (pintype "power_in"))
      (node (ref "U301") (pin "2") (pinfunction "GND_2") (pintype "bidirectional"))
      (node (ref "U302") (pin "13") (pinfunction "GND_13") (pintype "power_in"))
      (node (ref "U302") (pin "5") (pinfunction "TEST_5") (pintype "power_in"))
      (node (ref "U400") (pin "15") (pinfunction "TEST0_15") (pintype "bidirectional"))
      (node (ref "U400") (pin "16") (pinfunction "TEST1_16") (pintype "bidirectional"))
      (node (ref "U400") (pin "7") (pinfunction "GND_7") (pintype "power_in"))
      (node (ref "U400") (pin "EPAD") (pinfunction "GND_EPAD") (pintype "power_in"))
      (node (ref "U401") (pin "2") (pinfunction "GND_2") (pintype "bidirectional"))
      (node (ref "X101") (pin "2") (pinfunction "SHIELD_2") (pintype "power_in"))
      (node (ref "X101") (pin "4") (pinfunction "SHIELD_4") (pintype "power_in"))
    )
    (net (code "22") (name "I2C_SCL") (class "Default")
      (node (ref "U100") (pin "21") (pinfunction "PB10_21") (pintype "bidirectional"))
    )
    (net (code "23") (name "I2C_SDA") (class "Default")
      (node (ref "U100") (pin "22") (pinfunction "PB11_22") (pintype "bidirectional"))
    )
    (net (code "24") (name "MAG_CURR_FDB") (class "Default")
      (node (ref "C411") (pin "1") (pinfunction "1_1") (pintype "passive"))
      (node (ref "R413") (pin "2") (pinfunction "2_2") (pintype "passive"))
      (node (ref "U100") (pin "10") (pinfunction "PA0_10") (pintype "bidirectional"))
      (node (ref "U401") (pin "3") (pinfunction "OUT_3") (pintype "bidirectional"))
    )
    (net (code "25") (name "MAG_DIR") (class "Default")
      (node (ref "R403") (pin "2") (pinfunction "2_2") (pintype "passive"))
      (node (ref "U100") (pin "39") (pinfunction "PB3_39") (pintype "bidirectional"))
    )
    (net (code "26") (name "MAG_EN") (class "Default")
      (node (ref "R402") (pin "2") (pinfunction "2_2") (pintype "passive"))
      (node (ref "U100") (pin "46") (pinfunction "PB9_46") (pintype "bidirectional"))
    )
    (net (code "27") (name "MAG_FAULT") (class "Default")
      (node (ref "C405") (pin "1") (pinfunction "1_1") (pintype "passive"))
      (node (ref "R402") (pin "1") (pinfunction "1_1") (pintype "passive"))
      (node (ref "U100") (pin "45") (pinfunction "PB8_45") (pintype "bidirectional"))
      (node (ref "U400") (pin "13") (pinfunction "EN/FAULT_13") (pintype "bidirectional"))
    )
    (net (code "28") (name "MAG_PWM") (class "Default")
      (node (ref "R404") (pin "2") (pinfunction "2_2") (pintype "passive"))
      (node (ref "U100") (pin "38") (pinfunction "PA15_38") (pintype "bidirectional"))
    )
    (net (code "29") (name "MAG_STBY") (class "Default")
      (node (ref "C404") (pin "1") (pinfunction "1_1") (pintype "passive"))
      (node (ref "R401") (pin "2") (pinfunction "2_2") (pintype "passive"))
      (node (ref "TP3") (pin "TP") (pinfunction "TP_TP") (pintype "input"))
      (node (ref "U100") (pin "43") (pinfunction "PB7_43") (pintype "bidirectional"))
      (node (ref "U400") (pin "14") (pinfunction "STBY/RESET_14") (pintype "bidirectional"))
    )
    (net (code "30") (name "NRST") (class "Default")
      (node (ref "C106") (pin "1") (pinfunction "1_1") (pintype "passive"))
      (node (ref "C501") (pin "NRST") (pinfunction "7_NRST") (pintype "bidirectional"))
      (node (ref "U100") (pin "7") (pinfunction "NRST_7") (pintype "bidirectional"))
    )
    (net (code "31") (name "Net-(C407-Pad1)") (class "Default")
      (node (ref "C407") (pin "1") (pinfunction "1_1") (pintype "passive"))
      (node (ref "R407") (pin "2") (pinfunction "2_2") (pintype "passive"))
    )
    (net (code "32") (name "Net-(U100-PH0-OSC_IN)") (class "Default")
      (node (ref "C104") (pin "1") (pinfunction "1_1") (pintype "passive"))
      (node (ref "U100") (pin "5") (pinfunction "PH0-OSC_IN_5") (pintype "bidirectional"))
      (node (ref "X101") (pin "3") (pinfunction "2_3") (pintype "passive"))
    )
    (net (code "33") (name "Net-(U100-PH1-OSC_OUT)") (class "Default")
      (node (ref "C105") (pin "1") (pinfunction "1_1") (pintype "passive"))
      (node (ref "U100") (pin "6") (pinfunction "PH1-OSC_OUT_6") (pintype "bidirectional"))
      (node (ref "X101") (pin "1") (pinfunction "1_1") (pintype "passive"))
    )
    (net (code "34") (name "Net-(U200-EN)") (class "Default")
      (node (ref "R201") (pin "1") (pinfunction "1_1") (pintype "passive"))
      (node (ref "R202") (pin "2") (pinfunction "2_2") (pintype "passive"))
      (node (ref "U200") (pin "1") (pinfunction "PS/SYNC_1") (pintype "input"))
      (node (ref "U200") (pin "14") (pinfunction "EN_14") (pintype "input"))
    )
    (net (code "35") (name "Net-(U200-FB)") (class "Default")
      (node (ref "R204") (pin "1") (pinfunction "1_1") (pintype "passive"))
      (node (ref "R205") (pin "2") (pinfunction "2_2") (pintype "passive"))
      (node (ref "U200") (pin "5") (pinfunction "FB_5") (pintype "passive"))
    )
    (net (code "36") (name "Net-(U200-L1)") (class "Default")
      (node (ref "L201") (pin "1") (pinfunction "1_1") (pintype "passive"))
      (node (ref "U200") (pin "11") (pinfunction "L1_11") (pintype "passive"))
    )
    (net (code "37") (name "Net-(U200-L2)") (class "Default")
      (node (ref "L201") (pin "2") (pinfunction "2_2") (pintype "passive"))
      (node (ref "U200") (pin "9") (pinfunction "L2_9") (pintype "passive"))
    )
    (net (code "38") (name "Net-(U200-VAUX)") (class "Default")
      (node (ref "C204") (pin "1") (pinfunction "1_1") (pintype "passive"))
      (node (ref "U200") (pin "3") (pinfunction "VAUX_3") (pintype "output"))
    )
    (net (code "39") (name "Net-(U200-VSEL)") (class "Default")
      (node (ref "R203") (pin "2") (pinfunction "2_2") (pintype "passive"))
      (node (ref "U200") (pin "15") (pinfunction "VSEL_15") (pintype "input"))
    )
    (net (code "40") (name "Net-(U300-OUTU)") (class "Default")
      (node (ref "JP301") (pin "1") (pinfunction "1_1") (pintype "passive"))
      (node (ref "U300") (pin "3") (pinfunction "OUTU_3") (pintype "output"))
    )
    (net (code "41") (name "Net-(U300-OUTV)") (class "Default")
      (node (ref "JP301") (pin "2") (pinfunction "2_2") (pintype "passive"))
      (node (ref "U300") (pin "8") (pinfunction "OUTV_8") (pintype "output"))
    )
    (net (code "42") (name "Net-(U300-OUTW)") (class "Default")
      (node (ref "JP301") (pin "3") (pinfunction "3_3") (pintype "passive"))
      (node (ref "U300") (pin "10") (pinfunction "OUTW_10") (pintype "output"))
    )
    (net (code "43") (name "Net-(U300-SENSEU)") (class "Default")
      (node (ref "R304") (pin "1") (pinfunction "1_1") (pintype "passive"))
      (node (ref "R305") (pin "2") (pinfunction "2_2") (pintype "passive"))
      (node (ref "R306") (pin "2") (pinfunction "2_2") (pintype "passive"))
      (node (ref "U300") (pin "4") (pinfunction "SENSEU_4") (pintype "output"))
      (node (ref "U300") (pin "9") (pinfunction "SENSEVW_9") (pintype "output"))
    )
    (net (code "44") (name "Net-(U301-IN+)") (class "Default")
      (node (ref "C308") (pin "1") (pinfunction "1_1") (pintype "passive"))
      (node (ref "R303") (pin "1") (pinfunction "1_1") (pintype "passive"))
      (node (ref "R304") (pin "2") (pinfunction "2_2") (pintype "passive"))
      (node (ref "U301") (pin "1") (pinfunction "IN+_1") (pintype "bidirectional"))
    )
    (net (code "45") (name "Net-(U301-IN-)") (class "Default")
      (node (ref "C309") (pin "2") (pinfunction "2_2") (pintype "passive"))
      (node (ref "R307") (pin "1") (pinfunction "1_1") (pintype "passive"))
      (node (ref "R308") (pin "2") (pinfunction "2_2") (pintype "passive"))
      (node (ref "U301") (pin "5") (pinfunction "IN-_5") (pintype "bidirectional"))
    )
    (net (code "46") (name "Net-(U302-MOSI)") (class "Default")
      (node (ref "R309") (pin "2") (pinfunction "2_2") (pintype "passive"))
      (node (ref "U302") (pin "4") (pinfunction "MOSI_4") (pintype "input"))
    )
    (net (code "47") (name "Net-(U400-PH)") (class "Default")
      (node (ref "R403") (pin "1") (pinfunction "1_1") (pintype "passive"))
      (node (ref "U400") (pin "1") (pinfunction "PH_1") (pintype "input"))
    )
    (net (code "48") (name "Net-(U400-PWM)") (class "Default")
      (node (ref "R404") (pin "1") (pinfunction "1_1") (pintype "passive"))
      (node (ref "U400") (pin "2") (pinfunction "PWM_2") (pintype "input"))
    )
    (net (code "49") (name "Net-(U400-REF)") (class "Default")
      (node (ref "C406") (pin "1") (pinfunction "1_1") (pintype "passive"))
      (node (ref "R405") (pin "2") (pinfunction "2_2") (pintype "passive"))
      (node (ref "R406") (pin "1") (pinfunction "1_1") (pintype "passive"))
      (node (ref "U400") (pin "11") (pinfunction "REF_11") (pintype "passive"))
    )
    (net (code "50") (name "Net-(U400-SENSEA)") (class "Default")
      (node (ref "R410") (pin "1") (pinfunction "1_1") (pintype "passive"))
      (node (ref "R411") (pin "1") (pinfunction "1_1") (pintype "passive"))
      (node (ref "R412") (pin "1") (pinfunction "1_1") (pintype "passive"))
      (node (ref "U400") (pin "4") (pinfunction "SENSEA_4") (pintype "output"))
      (node (ref "U400") (pin "9") (pinfunction "SENSEB_9") (pintype "output"))
    )
    (net (code "51") (name "Net-(U400-TOFF)") (class "Default")
      (node (ref "R407") (pin "1") (pinfunction "1_1") (pintype "passive"))
      (node (ref "R408") (pin "1") (pinfunction "1_1") (pintype "passive"))
      (node (ref "U400") (pin "12") (pinfunction "TOFF_12") (pintype "passive"))
    )
    (net (code "52") (name "Net-(U401-IN+)") (class "Default")
      (node (ref "C410") (pin "1") (pinfunction "1_1") (pintype "passive"))
      (node (ref "R409") (pin "1") (pinfunction "1_1") (pintype "passive"))
      (node (ref "R410") (pin "2") (pinfunction "2_2") (pintype "passive"))
      (node (ref "U401") (pin "1") (pinfunction "IN+_1") (pintype "bidirectional"))
    )
    (net (code "53") (name "Net-(U401-IN-)") (class "Default")
      (node (ref "C411") (pin "2") (pinfunction "2_2") (pintype "passive"))
      (node (ref "R413") (pin "1") (pinfunction "1_1") (pintype "passive"))
      (node (ref "R414") (pin "2") (pinfunction "2_2") (pintype "passive"))
      (node (ref "U401") (pin "5") (pinfunction "IN-_5") (pintype "bidirectional"))
    )
    (net (code "54") (name "OUT1") (class "Default")
      (node (ref "CON502") (pin "10") (pinfunction "5_10") (pintype "bidirectional"))
      (node (ref "CON502") (pin "11") (pinfunction "5_11") (pintype "bidirectional"))
      (node (ref "U400") (pin "10") (pinfunction "OUTB1_10") (pintype "output"))
      (node (ref "U400") (pin "3") (pinfunction "OUTA1_3") (pintype "output"))
    )
    (net (code "55") (name "OUT2") (class "Default")
      (node (ref "CON502") (pin "8") (pinfunction "4_8") (pintype "bidirectional"))
      (node (ref "CON502") (pin "9") (pinfunction "4_9") (pintype "bidirectional"))
      (node (ref "U400") (pin "5") (pinfunction "OUTA2_5") (pintype "output"))
      (node (ref "U400") (pin "8") (pinfunction "OUTB2_8") (pintype "output"))
    )
    (net (code "56") (name "SPI1_CS") (class "Default")
      (node (ref "U100") (pin "14") (pinfunction "PA4_14") (pintype "bidirectional"))
      (node (ref "U302") (pin "1") (pinfunction "CSN_1") (pintype "input"))
    )
    (net (code "57") (name "SPI1_MISO") (class "Default")
      (node (ref "U100") (pin "16") (pinfunction "PA6_16") (pintype "bidirectional"))
      (node (ref "U302") (pin "3") (pinfunction "MISO_3") (pintype "output"))
    )
    (net (code "58") (name "SPI1_SCK") (class "Default")
      (node (ref "U100") (pin "15") (pinfunction "PA5_15") (pintype "bidirectional"))
      (node (ref "U302") (pin "2") (pinfunction "SCLK_2") (pintype "input"))
    )
    (net (code "59") (name "SWCLK") (class "Default")
      (node (ref "C501") (pin "SWCLK") (pinfunction "9_SWCLK") (pintype "bidirectional"))
      (node (ref "U100") (pin "37") (pinfunction "PA14_37") (pintype "bidirectional"))
    )
    (net (code "60") (name "SWDIO") (class "Default")
      (node (ref "C501") (pin "SWDIO") (pinfunction "8_SWDIO") (pintype "bidirectional"))
      (node (ref "U100") (pin "34") (pinfunction "PA13_34") (pintype "bidirectional"))
    )
    (net (code "61") (name "UART_RX") (class "Default")
      (node (ref "C501") (pin "UART_RX") (pinfunction "5_UART_RX") (pintype "bidirectional"))
      (node (ref "U100") (pin "13") (pinfunction "PA3_13") (pintype "bidirectional"))
    )
    (net (code "62") (name "UART_TX") (class "Default")
      (node (ref "C501") (pin "UART_TX") (pinfunction "6_UART_TX") (pintype "bidirectional"))
      (node (ref "U100") (pin "12") (pinfunction "PA2_12") (pintype "bidirectional"))
    )
    (net (code "63") (name "VBUS") (class "Default")
      (node (ref "C201") (pin "1") (pinfunction "1_1") (pintype "passive"))
      (node (ref "C202") (pin "1") (pinfunction "1_1") (pintype "passive"))
      (node (ref "C203") (pin "1") (pinfunction "1_1") (pintype "passive"))
      (node (ref "C301") (pin "1") (pinfunction "1_1") (pintype "passive"))
      (node (ref "C302") (pin "1") (pinfunction "1_1") (pintype "passive"))
      (node (ref "C303") (pin "1") (pinfunction "1_1") (pintype "passive"))
      (node (ref "C401") (pin "1") (pinfunction "1_1") (pintype "passive"))
      (node (ref "C402") (pin "1") (pinfunction "1_1") (pintype "passive"))
      (node (ref "C403") (pin "1") (pinfunction "1_1") (pintype "passive"))
      (node (ref "C501") (pin "VBUS") (pinfunction "1_VBUS") (pintype "bidirectional"))
      (node (ref "CON502") (pin "1") (pinfunction "1_1") (pintype "bidirectional"))
      (node (ref "CON502") (pin "2") (pinfunction "1_2") (pintype "bidirectional"))
      (node (ref "CON502") (pin "3") (pinfunction "1_3") (pintype "bidirectional"))
      (node (ref "R201") (pin "2") (pinfunction "2_2") (pintype "passive"))
      (node (ref "U200") (pin "12-13") (pinfunction "VIN_12-13") (pintype "power_in"))
      (node (ref "U300") (pin "6") (pinfunction "VS_6") (pintype "power_in"))
      (node (ref "U400") (pin "6") (pinfunction "VS_6") (pintype "power_in"))
    )
    (net (code "64") (name "unconnected-(U100-PA7-Pad17)") (class "Default")
      (node (ref "U100") (pin "17") (pinfunction "PA7_17") (pintype "bidirectional"))
    )
    (net (code "65") (name "unconnected-(U100-PB0-Pad18)") (class "Default")
      (node (ref "U100") (pin "18") (pinfunction "PB0_18") (pintype "bidirectional"))
    )
    (net (code "66") (name "unconnected-(U100-PC13-Pad2)") (class "Default")
      (node (ref "U100") (pin "2") (pinfunction "PC13_2") (pintype "bidirectional"))
    )
    (net (code "67") (name "unconnected-(U100-PC14-OSC32_IN-Pad3)") (class "Default")
      (node (ref "U100") (pin "3") (pinfunction "PC14-OSC32_IN_3") (pintype "bidirectional"))
    )
    (net (code "68") (name "unconnected-(U100-PC15-OSC32_OUT-Pad4)") (class "Default")
      (node (ref "U100") (pin "4") (pinfunction "PC15-OSC32_OUT_4") (pintype "bidirectional"))
    )
    (net (code "69") (name "unconnected-(U200-FB2-Pad6)") (class "Default")
      (node (ref "U200") (pin "6") (pinfunction "FB2_6") (pintype "passive"))
    )
    (net (code "70") (name "unconnected-(U200-PG-Pad2)") (class "Default")
      (node (ref "U200") (pin "2") (pinfunction "PG_2") (pintype "open_collector"))
    )
    (net (code "71") (name "unconnected-(U302-A-Pad7)") (class "Default")
      (node (ref "U302") (pin "7") (pinfunction "A_7") (pintype "output"))
    )
    (net (code "72") (name "unconnected-(U302-B-Pad6)") (class "Default")
      (node (ref "U302") (pin "6") (pinfunction "B_6") (pintype "output"))
    )
    (net (code "73") (name "unconnected-(U302-I{slash}PWM-Pad14)") (class "Default")
      (node (ref "U302") (pin "14") (pinfunction "I/PWM_14") (pintype "output"))
    )
    (net (code "74") (name "unconnected-(U302-U-Pad10)") (class "Default")
      (node (ref "U302") (pin "10") (pinfunction "U_10") (pintype "output"))
    )
    (net (code "75") (name "unconnected-(U302-V-Pad9)") (class "Default")
      (node (ref "U302") (pin "9") (pinfunction "V_9") (pintype "output"))
    )
    (net (code "76") (name "unconnected-(U302-W{slash}PWM-Pad8)") (class "Default")
      (node (ref "U302") (pin "8") (pinfunction "W/PWM_8") (pintype "output"))
    )
  )
)
